# CPU_module.net
KiCad netlist of a schematic drawn in EAGLE
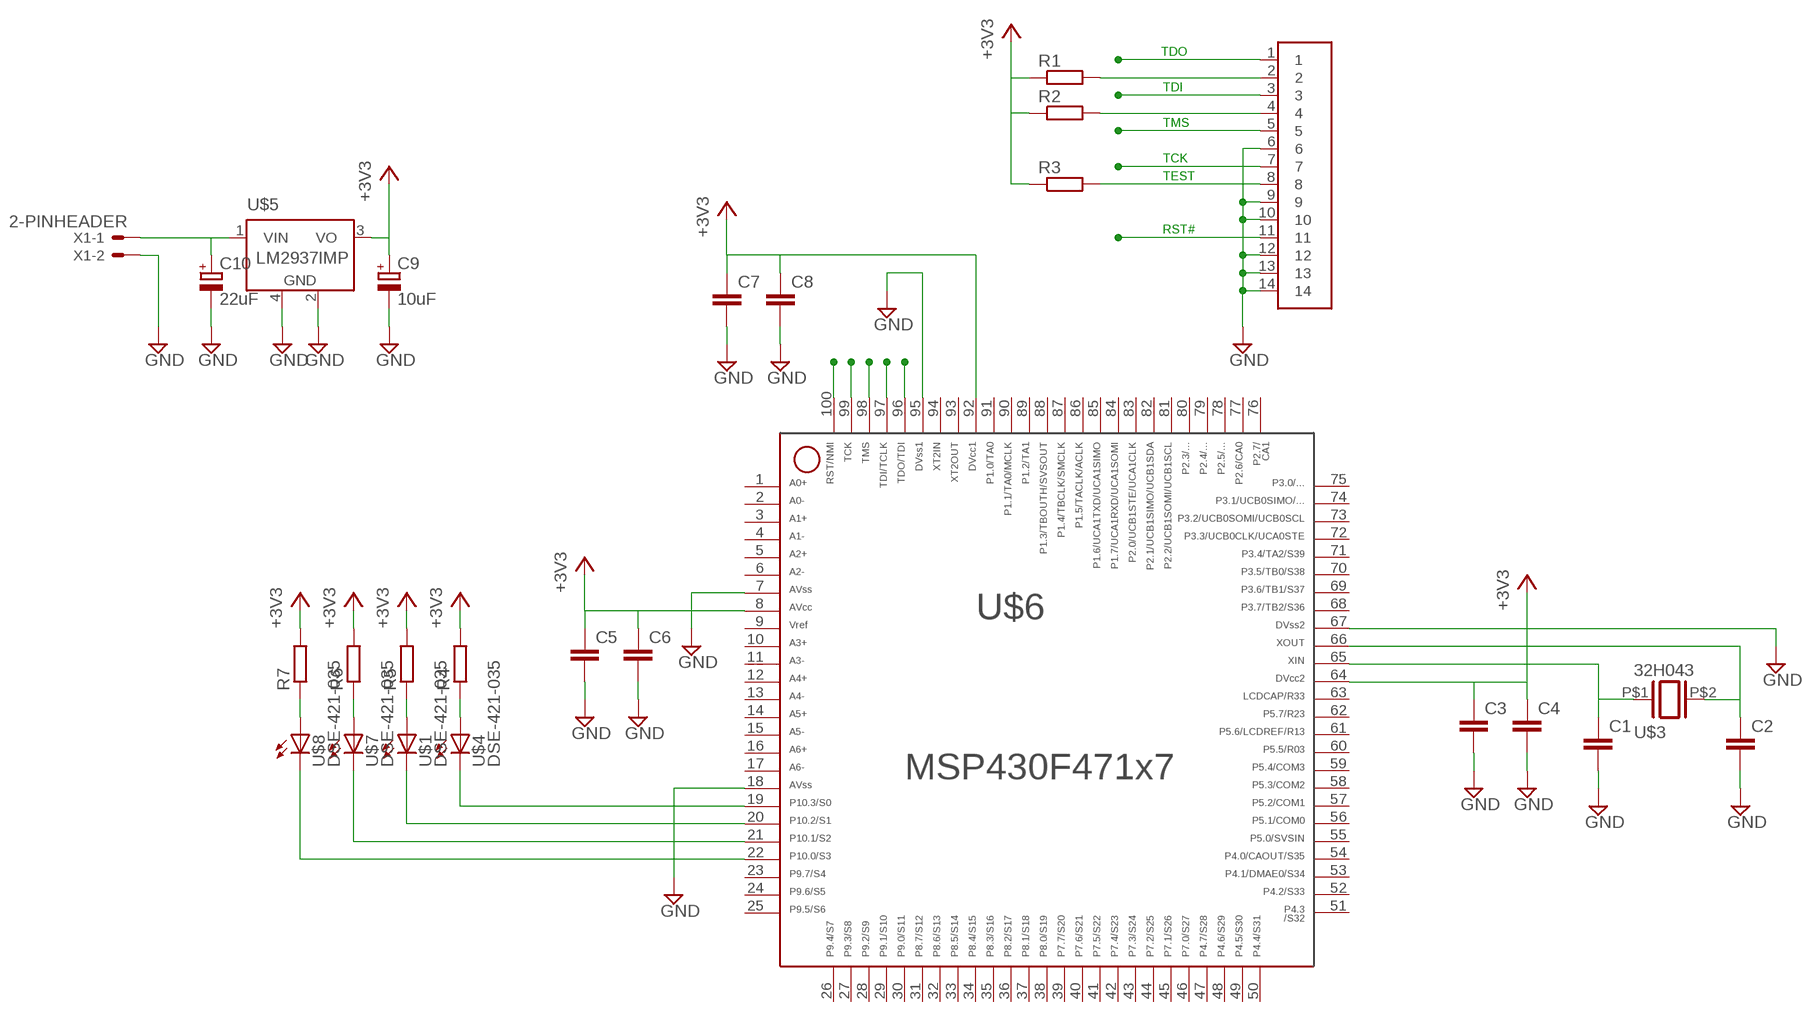
[diagram p0: schematic, sheet 1]

(export (version "E")
  (design (tool "Eeschema 10.0.6"))
  (components
    (comp (ref "C1")
      (value "C-EUC0402")
      (footprint "eagle-import:C0402")
      (libsource (lib "eagle-import") (part "C-EUC0402"))
    )
    (comp (ref "C2")
      (value "C-EUC0402")
      (footprint "eagle-import:C0402")
      (libsource (lib "eagle-import") (part "C-EUC0402"))
    )
    (comp (ref "C3")
      (value "C-EUC0402")
      (footprint "eagle-import:C0402")
      (libsource (lib "eagle-import") (part "C-EUC0402"))
    )
    (comp (ref "C4")
      (value "C-EUC0402")
      (footprint "eagle-import:C0402")
      (libsource (lib "eagle-import") (part "C-EUC0402"))
    )
    (comp (ref "C5")
      (value "C-EUC0402")
      (footprint "eagle-import:C0402")
      (libsource (lib "eagle-import") (part "C-EUC0402"))
    )
    (comp (ref "C6")
      (value "C-EUC0402")
      (footprint "eagle-import:C0402")
      (libsource (lib "eagle-import") (part "C-EUC0402"))
    )
    (comp (ref "C7")
      (value "C-EUC0402")
      (footprint "eagle-import:C0402")
      (libsource (lib "eagle-import") (part "C-EUC0402"))
    )
    (comp (ref "C8")
      (value "C-EUC0402")
      (footprint "eagle-import:C0402")
      (libsource (lib "eagle-import") (part "C-EUC0402"))
    )
    (comp (ref "C9")
      (value "10uF")
      (footprint "eagle-import:SMC_C")
      (libsource (lib "eagle-import") (part "CPOL-EUSMCC"))
    )
    (comp (ref "C10")
      (value "22uF")
      (footprint "eagle-import:SMC_D")
      (libsource (lib "eagle-import") (part "CPOL-EUSMCD"))
    )
    (comp (ref "R1")
      (value "R-EU_R0402")
      (footprint "eagle-import:R0402")
      (libsource (lib "eagle-import") (part "R-EU_R0402"))
    )
    (comp (ref "R2")
      (value "R-EU_R0402")
      (footprint "eagle-import:R0402")
      (libsource (lib "eagle-import") (part "R-EU_R0402"))
    )
    (comp (ref "R3")
      (value "R-EU_R0402")
      (footprint "eagle-import:R0402")
      (libsource (lib "eagle-import") (part "R-EU_R0402"))
    )
    (comp (ref "R4")
      (value "R-EU_R0402")
      (footprint "eagle-import:R0402")
      (libsource (lib "eagle-import") (part "R-EU_R0402"))
    )
    (comp (ref "R5")
      (value "R-EU_R0402")
      (footprint "eagle-import:R0402")
      (libsource (lib "eagle-import") (part "R-EU_R0402"))
    )
    (comp (ref "R6")
      (value "R-EU_R0402")
      (footprint "eagle-import:R0402")
      (libsource (lib "eagle-import") (part "R-EU_R0402"))
    )
    (comp (ref "R7")
      (value "R-EU_R0402")
      (footprint "eagle-import:R0402")
      (libsource (lib "eagle-import") (part "R-EU_R0402"))
    )
    (comp (ref "U$1")
      (value "DSE-421-035")
      (footprint "eagle-import:2432")
      (libsource (lib "eagle-import") (part "DSE-421-035"))
    )
    (comp (ref "U$2")
      (value "2X7SMD_HEADER")
      (footprint "eagle-import:2X14SMDPADS")
      (libsource (lib "eagle-import") (part "2X7SMD_HEADER"))
    )
    (comp (ref "U$3")
      (value "32H043")
      (footprint "eagle-import:XTAL-SMALL-4")
      (libsource (lib "eagle-import") (part "32H043"))
    )
    (comp (ref "U$4")
      (value "DSE-421-035")
      (footprint "eagle-import:2432")
      (libsource (lib "eagle-import") (part "DSE-421-035"))
    )
    (comp (ref "U$5")
      (value "LM2937IMP")
      (footprint "eagle-import:SOT223")
      (libsource (lib "eagle-import") (part "LM2937IMP"))
    )
    (comp (ref "U$6")
      (value "F471X7---PZ100")
      (footprint "eagle-import:PZ100")
      (libsource (lib "eagle-import") (part "F471X7---PZ100"))
    )
    (comp (ref "U$7")
      (value "DSE-421-035")
      (footprint "eagle-import:2432")
      (libsource (lib "eagle-import") (part "DSE-421-035"))
    )
    (comp (ref "U$8")
      (value "DSE-421-035")
      (footprint "eagle-import:2432")
      (libsource (lib "eagle-import") (part "DSE-421-035"))
    )
    (comp (ref "X1")
      (value "2-PINHEADER")
      (footprint "eagle-import:22-23-2021")
      (fields (field (name "MF") "MOLEX") (field (name "MPN") "22-23-2021"))
      (libsource (lib "eagle-import") (part "2-PINHEADER"))
    )
  )
  (nets
    (net (code "1") (name "+3V3") (class "Default")
      (node (ref "C3") (pin "1") (pinfunction "1_1") (pintype "passive"))
      (node (ref "C4") (pin "1") (pinfunction "1_1") (pintype "passive"))
      (node (ref "C5") (pin "1") (pinfunction "1_1") (pintype "passive"))
      (node (ref "C6") (pin "1") (pinfunction "1_1") (pintype "passive"))
      (node (ref "C7") (pin "1") (pinfunction "1_1") (pintype "passive"))
      (node (ref "C8") (pin "1") (pinfunction "1_1") (pintype "passive"))
      (node (ref "C9") (pin "+") (pinfunction "+_+") (pintype "passive"))
      (node (ref "R1") (pin "1") (pinfunction "1_1") (pintype "passive"))
      (node (ref "R2") (pin "1") (pinfunction "1_1") (pintype "passive"))
      (node (ref "R3") (pin "1") (pinfunction "1_1") (pintype "passive"))
      (node (ref "R4") (pin "2") (pinfunction "2_2") (pintype "passive"))
      (node (ref "R5") (pin "2") (pinfunction "2_2") (pintype "passive"))
      (node (ref "R6") (pin "2") (pinfunction "2_2") (pintype "passive"))
      (node (ref "R7") (pin "2") (pinfunction "2_2") (pintype "passive"))
      (node (ref "U$5") (pin "3") (pinfunction "VO_3") (pintype "passive"))
      (node (ref "U$6") (pin "64") (pinfunction "64_64") (pintype "power_in"))
      (node (ref "U$6") (pin "8") (pinfunction "8_8") (pintype "input"))
      (node (ref "U$6") (pin "92") (pinfunction "92_92") (pintype "power_in"))
    )
    (net (code "2") (name "/RST#") (class "Default")
      (node (ref "U$2") (pin "11") (pinfunction "11_11") (pintype "input"))
      (node (ref "U$6") (pin "100") (pinfunction "100_100") (pintype "input"))
    )
    (net (code "3") (name "/TCK") (class "Default")
      (node (ref "U$2") (pin "7") (pinfunction "7_7") (pintype "input"))
      (node (ref "U$6") (pin "99") (pinfunction "99_99") (pintype "input"))
    )
    (net (code "4") (name "/TDI") (class "Default")
      (node (ref "U$2") (pin "3") (pinfunction "3_3") (pintype "input"))
      (node (ref "U$6") (pin "97") (pinfunction "97_97") (pintype "input"))
    )
    (net (code "5") (name "/TDO") (class "Default")
      (node (ref "U$2") (pin "1") (pinfunction "1_1") (pintype "input"))
      (node (ref "U$6") (pin "96") (pinfunction "96_96") (pintype "bidirectional"))
    )
    (net (code "6") (name "/TMS") (class "Default")
      (node (ref "U$2") (pin "5") (pinfunction "5_5") (pintype "input"))
      (node (ref "U$6") (pin "98") (pinfunction "98_98") (pintype "input"))
    )
    (net (code "7") (name "GND") (class "Default")
      (node (ref "C1") (pin "2") (pinfunction "2_2") (pintype "passive"))
      (node (ref "C10") (pin "-") (pinfunction "-_-") (pintype "passive"))
      (node (ref "C2") (pin "2") (pinfunction "2_2") (pintype "passive"))
      (node (ref "C3") (pin "2") (pinfunction "2_2") (pintype "passive"))
      (node (ref "C4") (pin "2") (pinfunction "2_2") (pintype "passive"))
      (node (ref "C5") (pin "2") (pinfunction "2_2") (pintype "passive"))
      (node (ref "C6") (pin "2") (pinfunction "2_2") (pintype "passive"))
      (node (ref "C7") (pin "2") (pinfunction "2_2") (pintype "passive"))
      (node (ref "C8") (pin "2") (pinfunction "2_2") (pintype "passive"))
      (node (ref "C9") (pin "-") (pinfunction "-_-") (pintype "passive"))
      (node (ref "U$2") (pin "10") (pinfunction "10_10") (pintype "input"))
      (node (ref "U$2") (pin "12") (pinfunction "12_12") (pintype "input"))
      (node (ref "U$2") (pin "13") (pinfunction "13_13") (pintype "input"))
      (node (ref "U$2") (pin "14") (pinfunction "14_14") (pintype "input"))
      (node (ref "U$2") (pin "6") (pinfunction "6_6") (pintype "input"))
      (node (ref "U$2") (pin "9") (pinfunction "9_9") (pintype "input"))
      (node (ref "U$5") (pin "2") (pinfunction "GND_2") (pintype "passive"))
      (node (ref "U$5") (pin "4") (pinfunction "GND_4") (pintype "passive"))
      (node (ref "U$6") (pin "18") (pinfunction "18_18") (pintype "power_in"))
      (node (ref "U$6") (pin "67") (pinfunction "67_67") (pintype "power_in"))
      (node (ref "U$6") (pin "7") (pinfunction "7_7") (pintype "input"))
      (node (ref "U$6") (pin "95") (pinfunction "95_95") (pintype "power_in"))
      (node (ref "X1") (pin "2") (pinfunction "S_2") (pintype "passive"))
    )
    (net (code "8") (name "Net-(R1-Pad2)") (class "Default")
      (node (ref "R1") (pin "2") (pinfunction "2_2") (pintype "passive"))
      (node (ref "U$2") (pin "2") (pinfunction "2_2") (pintype "input"))
    )
    (net (code "9") (name "Net-(R2-Pad2)") (class "Default")
      (node (ref "R2") (pin "2") (pinfunction "2_2") (pintype "passive"))
      (node (ref "U$2") (pin "4") (pinfunction "4_4") (pintype "input"))
    )
    (net (code "10") (name "Net-(R3-Pad2)") (class "Default")
      (node (ref "R3") (pin "2") (pinfunction "2_2") (pintype "passive"))
      (node (ref "U$2") (pin "8") (pinfunction "8_8") (pintype "input"))
    )
    (net (code "11") (name "Net-(U$1-A)") (class "Default")
      (node (ref "R5") (pin "1") (pinfunction "1_1") (pintype "passive"))
      (node (ref "U$1") (pin "P$1") (pinfunction "A_P$1") (pintype "passive"))
    )
    (net (code "12") (name "Net-(U$1-C)") (class "Default")
      (node (ref "U$1") (pin "MARKED") (pinfunction "C_MARKED") (pintype "passive"))
      (node (ref "U$6") (pin "20") (pinfunction "20_20") (pintype "bidirectional"))
    )
    (net (code "13") (name "Net-(U$3-1)") (class "Default")
      (node (ref "C1") (pin "1") (pinfunction "1_1") (pintype "passive"))
      (node (ref "U$3") (pin "P$1") (pinfunction "1_P$1") (pintype "bidirectional"))
      (node (ref "U$6") (pin "65") (pinfunction "65_65") (pintype "input"))
    )
    (net (code "14") (name "Net-(U$3-2)") (class "Default")
      (node (ref "C2") (pin "1") (pinfunction "1_1") (pintype "passive"))
      (node (ref "U$3") (pin "P$2") (pinfunction "2_P$2") (pintype "bidirectional"))
      (node (ref "U$6") (pin "66") (pinfunction "66_66") (pintype "output"))
    )
    (net (code "15") (name "Net-(U$4-A)") (class "Default")
      (node (ref "R4") (pin "1") (pinfunction "1_1") (pintype "passive"))
      (node (ref "U$4") (pin "P$1") (pinfunction "A_P$1") (pintype "passive"))
    )
    (net (code "16") (name "Net-(U$4-C)") (class "Default")
      (node (ref "U$4") (pin "MARKED") (pinfunction "C_MARKED") (pintype "passive"))
      (node (ref "U$6") (pin "19") (pinfunction "19_19") (pintype "bidirectional"))
    )
    (net (code "17") (name "Net-(U$5-VIN)") (class "Default")
      (node (ref "C10") (pin "+") (pinfunction "+_+") (pintype "passive"))
      (node (ref "U$5") (pin "1") (pinfunction "VIN_1") (pintype "input"))
      (node (ref "X1") (pin "1") (pinfunction "S_1") (pintype "passive"))
    )
    (net (code "18") (name "Net-(U$7-A)") (class "Default")
      (node (ref "R6") (pin "1") (pinfunction "1_1") (pintype "passive"))
      (node (ref "U$7") (pin "P$1") (pinfunction "A_P$1") (pintype "passive"))
    )
    (net (code "19") (name "Net-(U$7-C)") (class "Default")
      (node (ref "U$6") (pin "21") (pinfunction "21_21") (pintype "bidirectional"))
      (node (ref "U$7") (pin "MARKED") (pinfunction "C_MARKED") (pintype "passive"))
    )
    (net (code "20") (name "Net-(U$8-A)") (class "Default")
      (node (ref "R7") (pin "1") (pinfunction "1_1") (pintype "passive"))
      (node (ref "U$8") (pin "P$1") (pinfunction "A_P$1") (pintype "passive"))
    )
    (net (code "21") (name "Net-(U$8-C)") (class "Default")
      (node (ref "U$6") (pin "22") (pinfunction "22_22") (pintype "bidirectional"))
      (node (ref "U$8") (pin "MARKED") (pinfunction "C_MARKED") (pintype "passive"))
    )
    (net (code "22") (name "unconnected-(U$6-Pad1)") (class "Default")
      (node (ref "U$6") (pin "1") (pinfunction "1_1") (pintype "input"))
    )
    (net (code "23") (name "unconnected-(U$6-Pad2)") (class "Default")
      (node (ref "U$6") (pin "2") (pinfunction "2_2") (pintype "input"))
    )
    (net (code "24") (name "unconnected-(U$6-Pad3)") (class "Default")
      (node (ref "U$6") (pin "3") (pinfunction "3_3") (pintype "input"))
    )
    (net (code "25") (name "unconnected-(U$6-Pad4)") (class "Default")
      (node (ref "U$6") (pin "4") (pinfunction "4_4") (pintype "input"))
    )
    (net (code "26") (name "unconnected-(U$6-Pad5)") (class "Default")
      (node (ref "U$6") (pin "5") (pinfunction "5_5") (pintype "input"))
    )
    (net (code "27") (name "unconnected-(U$6-Pad6)") (class "Default")
      (node (ref "U$6") (pin "6") (pinfunction "6_6") (pintype "input"))
    )
    (net (code "28") (name "unconnected-(U$6-Pad9)") (class "Default")
      (node (ref "U$6") (pin "9") (pinfunction "9_9") (pintype "bidirectional"))
    )
    (net (code "29") (name "unconnected-(U$6-Pad10)") (class "Default")
      (node (ref "U$6") (pin "10") (pinfunction "10_10") (pintype "input"))
    )
    (net (code "30") (name "unconnected-(U$6-Pad11)") (class "Default")
      (node (ref "U$6") (pin "11") (pinfunction "11_11") (pintype "input"))
    )
    (net (code "31") (name "unconnected-(U$6-Pad12)") (class "Default")
      (node (ref "U$6") (pin "12") (pinfunction "12_12") (pintype "input"))
    )
    (net (code "32") (name "unconnected-(U$6-Pad13)") (class "Default")
      (node (ref "U$6") (pin "13") (pinfunction "13_13") (pintype "input"))
    )
    (net (code "33") (name "unconnected-(U$6-Pad14)") (class "Default")
      (node (ref "U$6") (pin "14") (pinfunction "14_14") (pintype "input"))
    )
    (net (code "34") (name "unconnected-(U$6-Pad15)") (class "Default")
      (node (ref "U$6") (pin "15") (pinfunction "15_15") (pintype "input"))
    )
    (net (code "35") (name "unconnected-(U$6-Pad16)") (class "Default")
      (node (ref "U$6") (pin "16") (pinfunction "16_16") (pintype "input"))
    )
    (net (code "36") (name "unconnected-(U$6-Pad17)") (class "Default")
      (node (ref "U$6") (pin "17") (pinfunction "17_17") (pintype "input"))
    )
    (net (code "37") (name "unconnected-(U$6-Pad23)") (class "Default")
      (node (ref "U$6") (pin "23") (pinfunction "23_23") (pintype "bidirectional"))
    )
    (net (code "38") (name "unconnected-(U$6-Pad24)") (class "Default")
      (node (ref "U$6") (pin "24") (pinfunction "24_24") (pintype "bidirectional"))
    )
    (net (code "39") (name "unconnected-(U$6-Pad25)") (class "Default")
      (node (ref "U$6") (pin "25") (pinfunction "25_25") (pintype "bidirectional"))
    )
    (net (code "40") (name "unconnected-(U$6-Pad26)") (class "Default")
      (node (ref "U$6") (pin "26") (pinfunction "26_26") (pintype "bidirectional"))
    )
    (net (code "41") (name "unconnected-(U$6-Pad27)") (class "Default")
      (node (ref "U$6") (pin "27") (pinfunction "27_27") (pintype "bidirectional"))
    )
    (net (code "42") (name "unconnected-(U$6-Pad28)") (class "Default")
      (node (ref "U$6") (pin "28") (pinfunction "28_28") (pintype "bidirectional"))
    )
    (net (code "43") (name "unconnected-(U$6-Pad29)") (class "Default")
      (node (ref "U$6") (pin "29") (pinfunction "29_29") (pintype "bidirectional"))
    )
    (net (code "44") (name "unconnected-(U$6-Pad30)") (class "Default")
      (node (ref "U$6") (pin "30") (pinfunction "30_30") (pintype "bidirectional"))
    )
    (net (code "45") (name "unconnected-(U$6-Pad31)") (class "Default")
      (node (ref "U$6") (pin "31") (pinfunction "31_31") (pintype "bidirectional"))
    )
    (net (code "46") (name "unconnected-(U$6-Pad32)") (class "Default")
      (node (ref "U$6") (pin "32") (pinfunction "32_32") (pintype "bidirectional"))
    )
    (net (code "47") (name "unconnected-(U$6-Pad33)") (class "Default")
      (node (ref "U$6") (pin "33") (pinfunction "33_33") (pintype "bidirectional"))
    )
    (net (code "48") (name "unconnected-(U$6-Pad34)") (class "Default")
      (node (ref "U$6") (pin "34") (pinfunction "34_34") (pintype "bidirectional"))
    )
    (net (code "49") (name "unconnected-(U$6-Pad35)") (class "Default")
      (node (ref "U$6") (pin "35") (pinfunction "35_35") (pintype "bidirectional"))
    )
    (net (code "50") (name "unconnected-(U$6-Pad36)") (class "Default")
      (node (ref "U$6") (pin "36") (pinfunction "36_36") (pintype "bidirectional"))
    )
    (net (code "51") (name "unconnected-(U$6-Pad37)") (class "Default")
      (node (ref "U$6") (pin "37") (pinfunction "37_37") (pintype "bidirectional"))
    )
    (net (code "52") (name "unconnected-(U$6-Pad38)") (class "Default")
      (node (ref "U$6") (pin "38") (pinfunction "38_38") (pintype "bidirectional"))
    )
    (net (code "53") (name "unconnected-(U$6-Pad39)") (class "Default")
      (node (ref "U$6") (pin "39") (pinfunction "39_39") (pintype "bidirectional"))
    )
    (net (code "54") (name "unconnected-(U$6-Pad40)") (class "Default")
      (node (ref "U$6") (pin "40") (pinfunction "40_40") (pintype "bidirectional"))
    )
    (net (code "55") (name "unconnected-(U$6-Pad41)") (class "Default")
      (node (ref "U$6") (pin "41") (pinfunction "41_41") (pintype "bidirectional"))
    )
    (net (code "56") (name "unconnected-(U$6-Pad42)") (class "Default")
      (node (ref "U$6") (pin "42") (pinfunction "42_42") (pintype "bidirectional"))
    )
    (net (code "57") (name "unconnected-(U$6-Pad43)") (class "Default")
      (node (ref "U$6") (pin "43") (pinfunction "43_43") (pintype "bidirectional"))
    )
    (net (code "58") (name "unconnected-(U$6-Pad44)") (class "Default")
      (node (ref "U$6") (pin "44") (pinfunction "44_44") (pintype "bidirectional"))
    )
    (net (code "59") (name "unconnected-(U$6-Pad45)") (class "Default")
      (node (ref "U$6") (pin "45") (pinfunction "45_45") (pintype "bidirectional"))
    )
    (net (code "60") (name "unconnected-(U$6-Pad46)") (class "Default")
      (node (ref "U$6") (pin "46") (pinfunction "46_46") (pintype "bidirectional"))
    )
    (net (code "61") (name "unconnected-(U$6-Pad47)") (class "Default")
      (node (ref "U$6") (pin "47") (pinfunction "47_47") (pintype "bidirectional"))
    )
    (net (code "62") (name "unconnected-(U$6-Pad48)") (class "Default")
      (node (ref "U$6") (pin "48") (pinfunction "48_48") (pintype "bidirectional"))
    )
    (net (code "63") (name "unconnected-(U$6-Pad49)") (class "Default")
      (node (ref "U$6") (pin "49") (pinfunction "49_49") (pintype "bidirectional"))
    )
    (net (code "64") (name "unconnected-(U$6-Pad50)") (class "Default")
      (node (ref "U$6") (pin "50") (pinfunction "50_50") (pintype "bidirectional"))
    )
    (net (code "65") (name "unconnected-(U$6-Pad51)") (class "Default")
      (node (ref "U$6") (pin "51") (pinfunction "51_51") (pintype "bidirectional"))
    )
    (net (code "66") (name "unconnected-(U$6-Pad52)") (class "Default")
      (node (ref "U$6") (pin "52") (pinfunction "52_52") (pintype "bidirectional"))
    )
    (net (code "67") (name "unconnected-(U$6-Pad53)") (class "Default")
      (node (ref "U$6") (pin "53") (pinfunction "53_53") (pintype "bidirectional"))
    )
    (net (code "68") (name "unconnected-(U$6-Pad54)") (class "Default")
      (node (ref "U$6") (pin "54") (pinfunction "54_54") (pintype "bidirectional"))
    )
    (net (code "69") (name "unconnected-(U$6-Pad55)") (class "Default")
      (node (ref "U$6") (pin "55") (pinfunction "55_55") (pintype "bidirectional"))
    )
    (net (code "70") (name "unconnected-(U$6-Pad56)") (class "Default")
      (node (ref "U$6") (pin "56") (pinfunction "56_56") (pintype "bidirectional"))
    )
    (net (code "71") (name "unconnected-(U$6-Pad57)") (class "Default")
      (node (ref "U$6") (pin "57") (pinfunction "57_57") (pintype "bidirectional"))
    )
    (net (code "72") (name "unconnected-(U$6-Pad58)") (class "Default")
      (node (ref "U$6") (pin "58") (pinfunction "58_58") (pintype "bidirectional"))
    )
    (net (code "73") (name "unconnected-(U$6-Pad59)") (class "Default")
      (node (ref "U$6") (pin "59") (pinfunction "59_59") (pintype "bidirectional"))
    )
    (net (code "74") (name "unconnected-(U$6-Pad60)") (class "Default")
      (node (ref "U$6") (pin "60") (pinfunction "60_60") (pintype "bidirectional"))
    )
    (net (code "75") (name "unconnected-(U$6-Pad61)") (class "Default")
      (node (ref "U$6") (pin "61") (pinfunction "61_61") (pintype "bidirectional"))
    )
    (net (code "76") (name "unconnected-(U$6-Pad62)") (class "Default")
      (node (ref "U$6") (pin "62") (pinfunction "62_62") (pintype "bidirectional"))
    )
    (net (code "77") (name "unconnected-(U$6-Pad63)") (class "Default")
      (node (ref "U$6") (pin "63") (pinfunction "63_63") (pintype "input"))
    )
    (net (code "78") (name "unconnected-(U$6-Pad68)") (class "Default")
      (node (ref "U$6") (pin "68") (pinfunction "68_68") (pintype "bidirectional"))
    )
    (net (code "79") (name "unconnected-(U$6-Pad69)") (class "Default")
      (node (ref "U$6") (pin "69") (pinfunction "69_69") (pintype "bidirectional"))
    )
    (net (code "80") (name "unconnected-(U$6-Pad70)") (class "Default")
      (node (ref "U$6") (pin "70") (pinfunction "70_70") (pintype "bidirectional"))
    )
    (net (code "81") (name "unconnected-(U$6-Pad71)") (class "Default")
      (node (ref "U$6") (pin "71") (pinfunction "71_71") (pintype "bidirectional"))
    )
    (net (code "82") (name "unconnected-(U$6-Pad72)") (class "Default")
      (node (ref "U$6") (pin "72") (pinfunction "72_72") (pintype "bidirectional"))
    )
    (net (code "83") (name "unconnected-(U$6-Pad73)") (class "Default")
      (node (ref "U$6") (pin "73") (pinfunction "73_73") (pintype "bidirectional"))
    )
    (net (code "84") (name "unconnected-(U$6-Pad74)") (class "Default")
      (node (ref "U$6") (pin "74") (pinfunction "74_74") (pintype "bidirectional"))
    )
    (net (code "85") (name "unconnected-(U$6-Pad75)") (class "Default")
      (node (ref "U$6") (pin "75") (pinfunction "75_75") (pintype "bidirectional"))
    )
    (net (code "86") (name "unconnected-(U$6-Pad76)") (class "Default")
      (node (ref "U$6") (pin "76") (pinfunction "76_76") (pintype "bidirectional"))
    )
    (net (code "87") (name "unconnected-(U$6-Pad77)") (class "Default")
      (node (ref "U$6") (pin "77") (pinfunction "77_77") (pintype "bidirectional"))
    )
    (net (code "88") (name "unconnected-(U$6-Pad78)") (class "Default")
      (node (ref "U$6") (pin "78") (pinfunction "78_78") (pintype "bidirectional"))
    )
    (net (code "89") (name "unconnected-(U$6-Pad79)") (class "Default")
      (node (ref "U$6") (pin "79") (pinfunction "79_79") (pintype "bidirectional"))
    )
    (net (code "90") (name "unconnected-(U$6-Pad80)") (class "Default")
      (node (ref "U$6") (pin "80") (pinfunction "80_80") (pintype "bidirectional"))
    )
    (net (code "91") (name "unconnected-(U$6-Pad81)") (class "Default")
      (node (ref "U$6") (pin "81") (pinfunction "81_81") (pintype "bidirectional"))
    )
    (net (code "92") (name "unconnected-(U$6-Pad82)") (class "Default")
      (node (ref "U$6") (pin "82") (pinfunction "82_82") (pintype "bidirectional"))
    )
    (net (code "93") (name "unconnected-(U$6-Pad83)") (class "Default")
      (node (ref "U$6") (pin "83") (pinfunction "83_83") (pintype "bidirectional"))
    )
    (net (code "94") (name "unconnected-(U$6-Pad84)") (class "Default")
      (node (ref "U$6") (pin "84") (pinfunction "84_84") (pintype "bidirectional"))
    )
    (net (code "95") (name "unconnected-(U$6-Pad85)") (class "Default")
      (node (ref "U$6") (pin "85") (pinfunction "85_85") (pintype "bidirectional"))
    )
    (net (code "96") (name "unconnected-(U$6-Pad86)") (class "Default")
      (node (ref "U$6") (pin "86") (pinfunction "86_86") (pintype "bidirectional"))
    )
    (net (code "97") (name "unconnected-(U$6-Pad87)") (class "Default")
      (node (ref "U$6") (pin "87") (pinfunction "87_87") (pintype "bidirectional"))
    )
    (net (code "98") (name "unconnected-(U$6-Pad88)") (class "Default")
      (node (ref "U$6") (pin "88") (pinfunction "88_88") (pintype "bidirectional"))
    )
    (net (code "99") (name "unconnected-(U$6-Pad89)") (class "Default")
      (node (ref "U$6") (pin "89") (pinfunction "89_89") (pintype "bidirectional"))
    )
    (net (code "100") (name "unconnected-(U$6-Pad90)") (class "Default")
      (node (ref "U$6") (pin "90") (pinfunction "90_90") (pintype "bidirectional"))
    )
    (net (code "101") (name "unconnected-(U$6-Pad91)") (class "Default")
      (node (ref "U$6") (pin "91") (pinfunction "91_91") (pintype "bidirectional"))
    )
    (net (code "102") (name "unconnected-(U$6-Pad93)") (class "Default")
      (node (ref "U$6") (pin "93") (pinfunction "93_93") (pintype "output"))
    )
    (net (code "103") (name "unconnected-(U$6-Pad94)") (class "Default")
      (node (ref "U$6") (pin "94") (pinfunction "94_94") (pintype "input"))
    )
  )
)
